# OpenSpindle.net
KiCad netlist of a schematic drawn in EAGLE
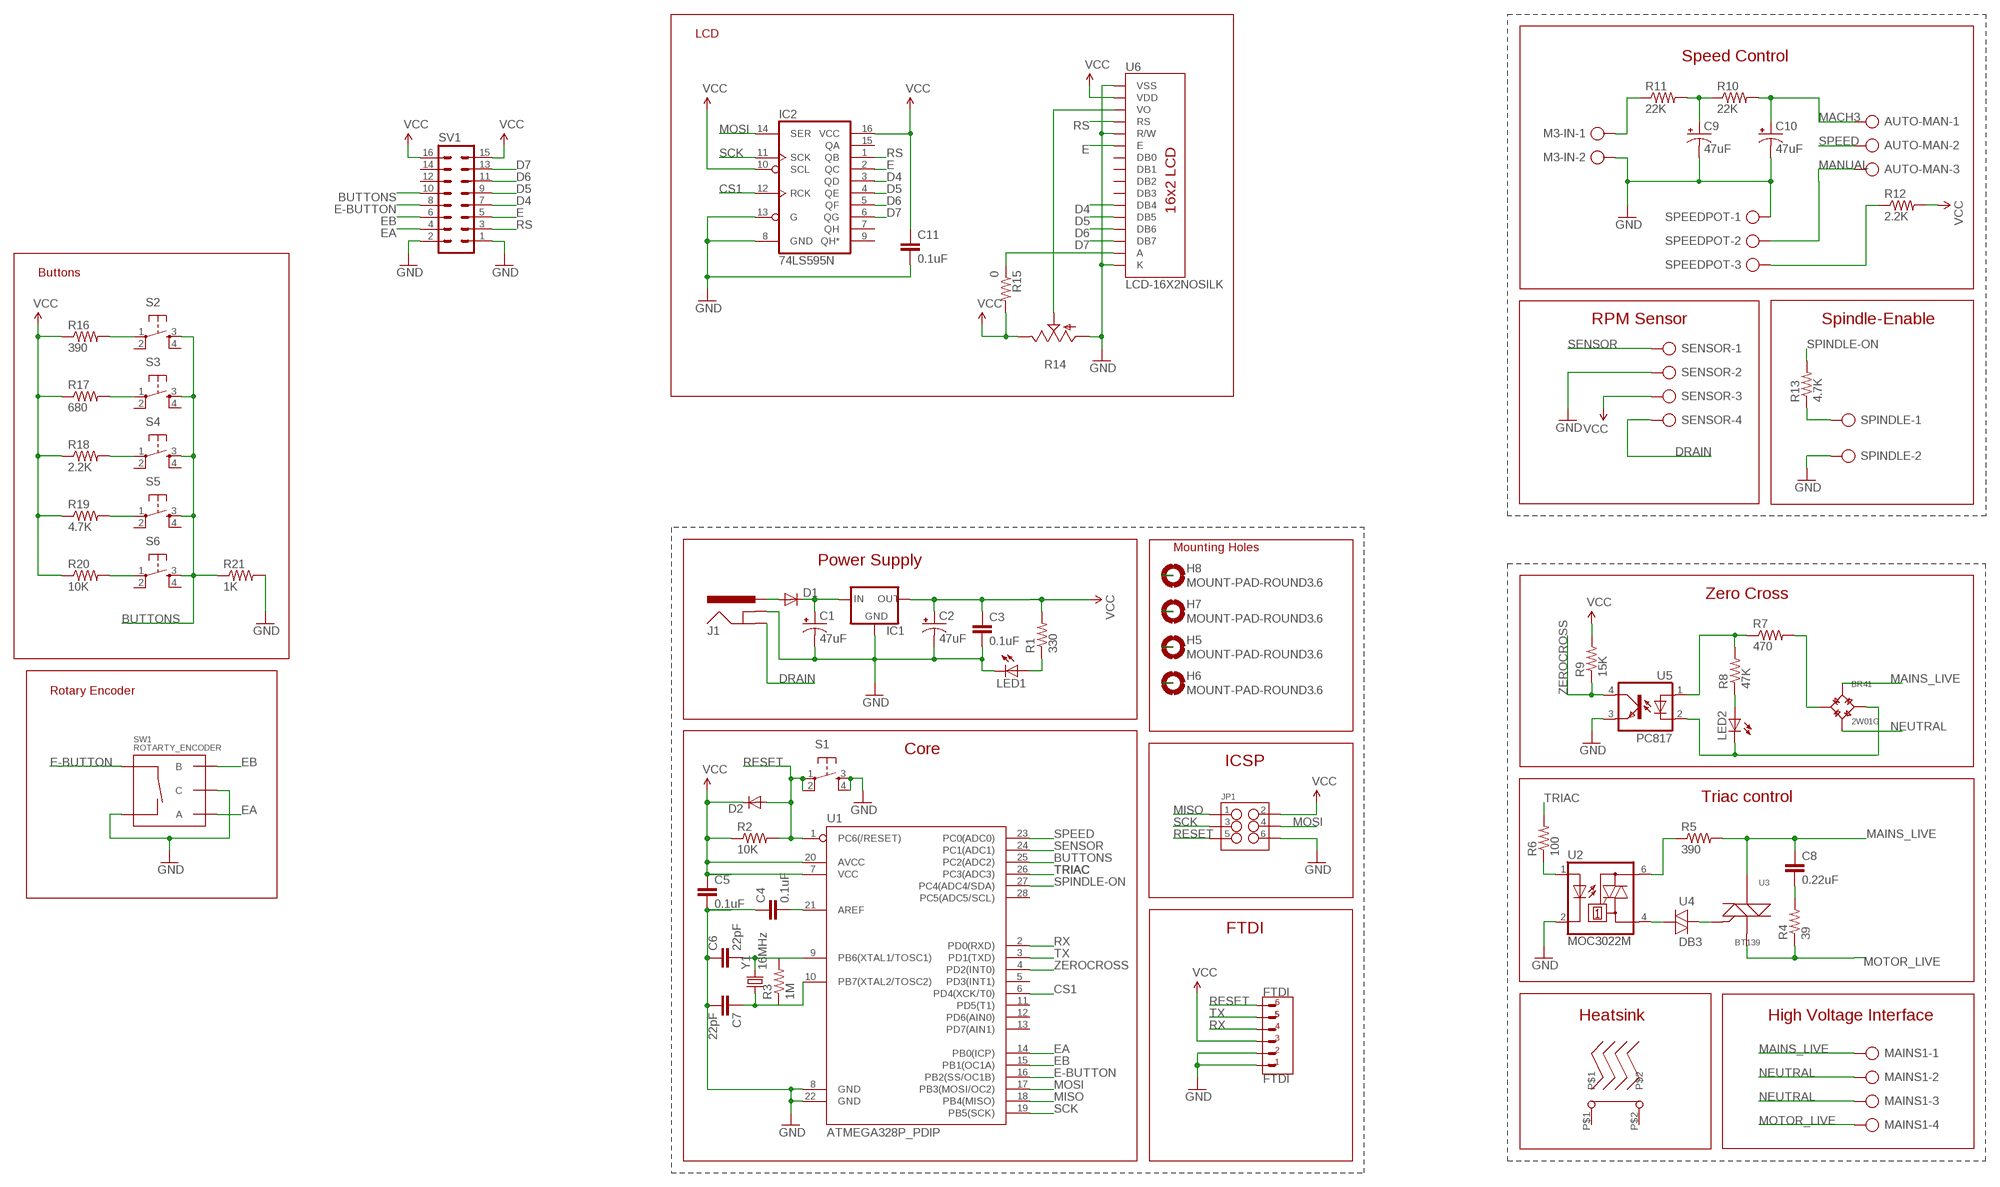
[diagram p0: schematic, sheet 1]

(export (version "E")
  (design (tool "Eeschema 10.0.6"))
  (components
    (comp (ref "AUTO-MAN")
      (value "AK500/3")
      (footprint "eagle-import:AK500_3")
      (libsource (lib "eagle-import") (part "AK500/3"))
    )
    (comp (ref "BR41")
      (value "2W01G")
      (footprint "eagle-import:DIODEBRIDGE")
      (libsource (lib "eagle-import") (part "DIODEBRIDGE"))
    )
    (comp (ref "C1")
      (value "47uF")
      (footprint "eagle-import:CPOL-RADIAL-10UF-25V")
      (libsource (lib "eagle-import") (part "CAP_POLPTH2"))
    )
    (comp (ref "C2")
      (value "47uF")
      (footprint "eagle-import:CPOL-RADIAL-10UF-25V")
      (libsource (lib "eagle-import") (part "CAP_POLPTH2"))
    )
    (comp (ref "C3")
      (value "0.1uF")
      (footprint "eagle-import:CAP-PTH-SMALL")
      (libsource (lib "eagle-import") (part "SparkFun-Capacitors_CAPPTH"))
    )
    (comp (ref "C4")
      (value "0.1uF")
      (footprint "eagle-import:CAP-PTH-SMALL")
      (libsource (lib "eagle-import") (part "SparkFun-Capacitors_CAPPTH"))
    )
    (comp (ref "C5")
      (value "0.1uF")
      (footprint "eagle-import:CAP-PTH-SMALL")
      (libsource (lib "eagle-import") (part "SparkFun-Capacitors_CAPPTH"))
    )
    (comp (ref "C6")
      (value "22pF")
      (footprint "eagle-import:CAP-PTH-SMALL")
      (libsource (lib "eagle-import") (part "SparkFun-Capacitors_CAPPTH"))
    )
    (comp (ref "C7")
      (value "22pF")
      (footprint "eagle-import:CAP-PTH-SMALL")
      (libsource (lib "eagle-import") (part "SparkFun-Capacitors_CAPPTH"))
    )
    (comp (ref "C8")
      (value "0.22uF")
      (footprint "eagle-import:CAP-PTH-SMALL")
      (libsource (lib "eagle-import") (part "CAPPTH"))
    )
    (comp (ref "C9")
      (value "47uF")
      (footprint "eagle-import:CPOL-RADIAL-10UF-25V")
      (libsource (lib "eagle-import") (part "CAP_POLPTH2"))
    )
    (comp (ref "C10")
      (value "47uF")
      (footprint "eagle-import:CPOL-RADIAL-10UF-25V")
      (libsource (lib "eagle-import") (part "CAP_POLPTH2"))
    )
    (comp (ref "C11")
      (value "0.1uF")
      (footprint "eagle-import:CAP-PTH-SMALL")
      (libsource (lib "eagle-import") (part "SparkFun-Capacitors_CAPPTH"))
    )
    (comp (ref "D1")
      (value "DIODEPTH")
      (footprint "eagle-import:DIODE-1N4001")
      (libsource (lib "eagle-import") (part "DIODEPTH"))
    )
    (comp (ref "D2")
      (value "DIODEPTH")
      (footprint "eagle-import:DIODE-1N4001")
      (libsource (lib "eagle-import") (part "DIODEPTH"))
    )
    (comp (ref "FTDI")
      (value "FTDI")
      (footprint "eagle-import:6PINHEADER")
      (libsource (lib "eagle-import") (part "6PINHEADER0.1{dblquote}"))
    )
    (comp (ref "H5")
      (value "MOUNT-PAD-ROUND3.6")
      (footprint "eagle-import:3,6-PAD")
      (libsource (lib "eagle-import") (part "MOUNT-PAD-ROUND3.6"))
    )
    (comp (ref "H6")
      (value "MOUNT-PAD-ROUND3.6")
      (footprint "eagle-import:3,6-PAD")
      (libsource (lib "eagle-import") (part "MOUNT-PAD-ROUND3.6"))
    )
    (comp (ref "H7")
      (value "MOUNT-PAD-ROUND3.6")
      (footprint "eagle-import:3,6-PAD")
      (libsource (lib "eagle-import") (part "MOUNT-PAD-ROUND3.6"))
    )
    (comp (ref "H8")
      (value "MOUNT-PAD-ROUND3.6")
      (footprint "eagle-import:3,6-PAD")
      (libsource (lib "eagle-import") (part "MOUNT-PAD-ROUND3.6"))
    )
    (comp (ref "IC1")
      (value "V_REG_78XX-TO-220")
      (footprint "eagle-import:TO-220-ALT")
      (libsource (lib "eagle-import") (part "V_REG_78XX-TO-220"))
    )
    (comp (ref "IC2")
      (value "74LS595N")
      (footprint "eagle-import:DIL16")
      (libsource (lib "eagle-import") (part "74595NLS"))
    )
    (comp (ref "J1")
      (value "POWER_JACKPTH_LOCK")
      (footprint "eagle-import:POWER_JACK_PTH_LOCK")
      (libsource (lib "eagle-import") (part "POWER_JACKPTH_LOCK"))
    )
    (comp (ref "JP1")
      (value "M03X2POGO_PINS")
      (footprint "eagle-import:2X3_POGO")
      (libsource (lib "eagle-import") (part "M03X2POGO_PINS"))
    )
    (comp (ref "LED1")
      (value "LED5MM")
      (footprint "eagle-import:LED5MM")
      (libsource (lib "eagle-import") (part "adafruit2012_LED5MM"))
    )
    (comp (ref "LED2")
      (value "LED5MM")
      (footprint "eagle-import:LED5MM")
      (libsource (lib "eagle-import") (part "LED5MM"))
    )
    (comp (ref "M3-IN")
      (value "AK500/2")
      (footprint "eagle-import:AK500_2")
      (libsource (lib "eagle-import") (part "AK500/2"))
    )
    (comp (ref "MAINS1")
      (value "AK500/4")
      (footprint "eagle-import:AK500_4")
      (libsource (lib "eagle-import") (part "AK500/4"))
    )
    (comp (ref "R1")
      (value "330")
      (footprint "eagle-import:AXIAL-0.3")
      (libsource (lib "eagle-import") (part "RESISTORAXIAL-0.3"))
    )
    (comp (ref "R2")
      (value "10K")
      (footprint "eagle-import:AXIAL-0.3")
      (libsource (lib "eagle-import") (part "RESISTORAXIAL-0.3"))
    )
    (comp (ref "R3")
      (value "1M")
      (footprint "eagle-import:AXIAL-0.3")
      (libsource (lib "eagle-import") (part "RESISTORAXIAL-0.3"))
    )
    (comp (ref "R4")
      (value "39")
      (footprint "eagle-import:AXIAL-0.3")
      (libsource (lib "eagle-import") (part "RESISTORAXIAL-0.3"))
    )
    (comp (ref "R5")
      (value "390")
      (footprint "eagle-import:AXIAL-0.3")
      (libsource (lib "eagle-import") (part "RESISTORAXIAL-0.3"))
    )
    (comp (ref "R6")
      (value "100")
      (footprint "eagle-import:AXIAL-0.3")
      (libsource (lib "eagle-import") (part "RESISTORAXIAL-0.3"))
    )
    (comp (ref "R7")
      (value "470")
      (footprint "eagle-import:SQM_5-10")
      (libsource (lib "eagle-import") (part "RESISTORM_5-10"))
    )
    (comp (ref "R8")
      (value "47K")
      (footprint "eagle-import:SQM_5-10")
      (libsource (lib "eagle-import") (part "RESISTORM_5-10"))
    )
    (comp (ref "R9")
      (value "15K")
      (footprint "eagle-import:AXIAL-0.3")
      (libsource (lib "eagle-import") (part "RESISTORAXIAL-0.3"))
    )
    (comp (ref "R10")
      (value "22K")
      (footprint "eagle-import:AXIAL-0.3")
      (libsource (lib "eagle-import") (part "RESISTORAXIAL-0.3"))
    )
    (comp (ref "R11")
      (value "22K")
      (footprint "eagle-import:AXIAL-0.3")
      (libsource (lib "eagle-import") (part "RESISTORAXIAL-0.3"))
    )
    (comp (ref "R12")
      (value "2.2K")
      (footprint "eagle-import:AXIAL-0.3")
      (libsource (lib "eagle-import") (part "RESISTORAXIAL-0.3"))
    )
    (comp (ref "R13")
      (value "4.7K")
      (footprint "eagle-import:AXIAL-0.3")
      (libsource (lib "eagle-import") (part "RESISTORAXIAL-0.3"))
    )
    (comp (ref "R14")
      (value "POT_TRIM_US-B25U")
      (footprint "eagle-import:POT_B25U")
      (libsource (lib "eagle-import") (part "POT_TRIM_US-B25U"))
    )
    (comp (ref "R15")
      (value "0")
      (footprint "eagle-import:AXIAL-0.3")
      (libsource (lib "eagle-import") (part "RESISTORAXIAL-0.3"))
    )
    (comp (ref "R16")
      (value "390")
      (footprint "eagle-import:AXIAL-0.3")
      (libsource (lib "eagle-import") (part "RESISTORAXIAL-0.3"))
    )
    (comp (ref "R17")
      (value "680")
      (footprint "eagle-import:AXIAL-0.3")
      (libsource (lib "eagle-import") (part "RESISTORAXIAL-0.3"))
    )
    (comp (ref "R18")
      (value "2.2K")
      (footprint "eagle-import:AXIAL-0.3")
      (libsource (lib "eagle-import") (part "RESISTORAXIAL-0.3"))
    )
    (comp (ref "R19")
      (value "4.7K")
      (footprint "eagle-import:AXIAL-0.3")
      (libsource (lib "eagle-import") (part "RESISTORAXIAL-0.3"))
    )
    (comp (ref "R20")
      (value "10K")
      (footprint "eagle-import:AXIAL-0.3")
      (libsource (lib "eagle-import") (part "RESISTORAXIAL-0.3"))
    )
    (comp (ref "R21")
      (value "1K")
      (footprint "eagle-import:AXIAL-0.3")
      (libsource (lib "eagle-import") (part "RESISTORAXIAL-0.3"))
    )
    (comp (ref "S1")
      (value "TAC_SWITCHPTH")
      (footprint "eagle-import:TACTILE-PTH")
      (libsource (lib "eagle-import") (part "TAC_SWITCHPTH"))
    )
    (comp (ref "S2")
      (value "TAC_SWITCHPTH")
      (footprint "eagle-import:TACTILE-PTH")
      (libsource (lib "eagle-import") (part "TAC_SWITCHPTH"))
    )
    (comp (ref "S3")
      (value "TAC_SWITCHPTH")
      (footprint "eagle-import:TACTILE-PTH")
      (libsource (lib "eagle-import") (part "TAC_SWITCHPTH"))
    )
    (comp (ref "S4")
      (value "TAC_SWITCHPTH")
      (footprint "eagle-import:TACTILE-PTH")
      (libsource (lib "eagle-import") (part "TAC_SWITCHPTH"))
    )
    (comp (ref "S5")
      (value "TAC_SWITCHPTH")
      (footprint "eagle-import:TACTILE-PTH")
      (libsource (lib "eagle-import") (part "TAC_SWITCHPTH"))
    )
    (comp (ref "S6")
      (value "TAC_SWITCHPTH")
      (footprint "eagle-import:TACTILE-PTH")
      (libsource (lib "eagle-import") (part "TAC_SWITCHPTH"))
    )
    (comp (ref "SENSOR")
      (value "AK500/4")
      (footprint "eagle-import:AK500_4")
      (libsource (lib "eagle-import") (part "AK500/4"))
    )
    (comp (ref "SPEEDPOT")
      (value "AK500/3")
      (footprint "eagle-import:AK500_3")
      (libsource (lib "eagle-import") (part "AK500/3"))
    )
    (comp (ref "SPINDLE")
      (value "AK500/2")
      (footprint "eagle-import:AK500_2")
      (libsource (lib "eagle-import") (part "AK500/2"))
    )
    (comp (ref "SV1")
      (value "ML16")
      (footprint "eagle-import:ML16")
      (libsource (lib "eagle-import") (part "ML16"))
    )
    (comp (ref "SW1")
      (value "ROTARTY_ENCODER")
      (footprint "eagle-import:ROTARY_ENC_PLAIN")
      (libsource (lib "eagle-import") (part "ROTARTY_ENCODER"))
    )
    (comp (ref "U$2")
      (value "HEATSINK529802B02500G")
      (footprint "eagle-import:529802B02500G")
      (libsource (lib "eagle-import") (part "HEATSINK529802B02500G"))
    )
    (comp (ref "U1")
      (value "ATMEGA328P_PDIP")
      (footprint "eagle-import:DIL28-3")
      (libsource (lib "eagle-import") (part "ATMEGA328P_PDIP"))
    )
    (comp (ref "U2")
      (value "MOC3022M")
      (footprint "eagle-import:DIL06")
      (fields (field (name "MF") "FAIRCHILD SEMICONDUCTOR") (field (name "MPN") "MOC3022-M"))
      (libsource (lib "eagle-import") (part "MOC30M22"))
    )
    (comp (ref "U3")
      (value "BT139")
      (footprint "eagle-import:TRIAC")
      (libsource (lib "eagle-import") (part "TRIAC"))
    )
    (comp (ref "U4")
      (value "DB3")
      (footprint "eagle-import:DO35-10")
      (libsource (lib "eagle-import") (part "DIAC-DO35-10"))
    )
    (comp (ref "U5")
      (value "PC817")
      (footprint "eagle-import:DIL04")
      (fields (field (name "MPN") "PC817X4J000F"))
      (libsource (lib "eagle-import") (part "PC817"))
    )
    (comp (ref "U6")
      (value "LCD-16X2NOSILK")
      (footprint "eagle-import:LCD-16X2_NOSILK")
      (libsource (lib "eagle-import") (part "LCD-16X2NOSILK"))
    )
    (comp (ref "Y1")
      (value "16MHz")
      (footprint "eagle-import:HC49U-V")
      (libsource (lib "eagle-import") (part "CRYSTALHC49UV"))
    )
  )
  (nets
    (net (code "1") (name "/BUTTONS") (class "Default")
      (node (ref "R21") (pin "P$1") (pinfunction "1_P$1") (pintype "passive"))
      (node (ref "S2") (pin "3") (pinfunction "3_3") (pintype "passive"))
      (node (ref "S3") (pin "3") (pinfunction "3_3") (pintype "passive"))
      (node (ref "S4") (pin "3") (pinfunction "3_3") (pintype "passive"))
      (node (ref "S5") (pin "3") (pinfunction "3_3") (pintype "passive"))
      (node (ref "S6") (pin "3") (pinfunction "3_3") (pintype "passive"))
      (node (ref "SV1") (pin "10") (pinfunction "10_10") (pintype "passive"))
      (node (ref "U1") (pin "25") (pinfunction "PC2(ADC2)_25") (pintype "bidirectional"))
    )
    (net (code "2") (name "/CS1") (class "Default")
      (node (ref "IC2") (pin "12") (pinfunction "RCK_12") (pintype "input"))
      (node (ref "U1") (pin "6") (pinfunction "PD4(XCK/T0)_6") (pintype "bidirectional"))
    )
    (net (code "3") (name "/D4") (class "Default")
      (node (ref "IC2") (pin "3") (pinfunction "QD_3") (pintype "tri_state"))
      (node (ref "SV1") (pin "7") (pinfunction "7_7") (pintype "passive"))
      (node (ref "U6") (pin "11") (pinfunction "DB4_11") (pintype "bidirectional"))
    )
    (net (code "4") (name "/D5") (class "Default")
      (node (ref "IC2") (pin "4") (pinfunction "QE_4") (pintype "tri_state"))
      (node (ref "SV1") (pin "9") (pinfunction "9_9") (pintype "passive"))
      (node (ref "U6") (pin "12") (pinfunction "DB5_12") (pintype "bidirectional"))
    )
    (net (code "5") (name "/D6") (class "Default")
      (node (ref "IC2") (pin "5") (pinfunction "QF_5") (pintype "tri_state"))
      (node (ref "SV1") (pin "11") (pinfunction "11_11") (pintype "passive"))
      (node (ref "U6") (pin "13") (pinfunction "DB6_13") (pintype "bidirectional"))
    )
    (net (code "6") (name "/D7") (class "Default")
      (node (ref "IC2") (pin "6") (pinfunction "QG_6") (pintype "tri_state"))
      (node (ref "SV1") (pin "13") (pinfunction "13_13") (pintype "passive"))
      (node (ref "U6") (pin "14") (pinfunction "DB7_14") (pintype "bidirectional"))
    )
    (net (code "7") (name "/DRAIN") (class "Default")
      (node (ref "J1") (pin "GND") (pinfunction "GND_GND") (pintype "bidirectional"))
      (node (ref "SENSOR") (pin "4") (pinfunction "KL_4") (pintype "passive"))
    )
    (net (code "8") (name "/E") (class "Default")
      (node (ref "IC2") (pin "2") (pinfunction "QC_2") (pintype "tri_state"))
      (node (ref "SV1") (pin "5") (pinfunction "5_5") (pintype "passive"))
      (node (ref "U6") (pin "6") (pinfunction "E_6") (pintype "input"))
    )
    (net (code "9") (name "/E-BUTTON") (class "Default")
      (node (ref "SV1") (pin "8") (pinfunction "8_8") (pintype "passive"))
      (node (ref "SW1") (pin "SW+") (pinfunction "SW+_SW+") (pintype "bidirectional"))
      (node (ref "U1") (pin "16") (pinfunction "PB2(SS/OC1B)_16") (pintype "bidirectional"))
    )
    (net (code "10") (name "/EA") (class "Default")
      (node (ref "SV1") (pin "4") (pinfunction "4_4") (pintype "passive"))
      (node (ref "SW1") (pin "A") (pinfunction "A_A") (pintype "bidirectional"))
      (node (ref "U1") (pin "14") (pinfunction "PB0(ICP)_14") (pintype "bidirectional"))
    )
    (net (code "11") (name "/EB") (class "Default")
      (node (ref "SV1") (pin "6") (pinfunction "6_6") (pintype "passive"))
      (node (ref "SW1") (pin "B") (pinfunction "B_B") (pintype "bidirectional"))
      (node (ref "U1") (pin "15") (pinfunction "PB1(OC1A)_15") (pintype "bidirectional"))
    )
    (net (code "12") (name "/MACH3") (class "Default")
      (node (ref "AUTO-MAN") (pin "1") (pinfunction "KL_1") (pintype "passive"))
      (node (ref "C10") (pin "1") (pinfunction "+_1") (pintype "passive"))
      (node (ref "R10") (pin "P$2") (pinfunction "2_P$2") (pintype "passive"))
    )
    (net (code "13") (name "/MAINS_LIVE") (class "Default")
      (node (ref "BR41") (pin "AC1") (pinfunction "AC1_AC1") (pintype "bidirectional"))
      (node (ref "C8") (pin "1") (pinfunction "1_1") (pintype "passive"))
      (node (ref "MAINS1") (pin "1") (pinfunction "KL_1") (pintype "passive"))
      (node (ref "R5") (pin "P$2") (pinfunction "2_P$2") (pintype "passive"))
      (node (ref "U3") (pin "2") (pinfunction "A_2") (pintype "bidirectional"))
    )
    (net (code "14") (name "/MANUAL") (class "Default")
      (node (ref "AUTO-MAN") (pin "3") (pinfunction "KL_3") (pintype "passive"))
      (node (ref "SPEEDPOT") (pin "2") (pinfunction "KL_2") (pintype "passive"))
    )
    (net (code "15") (name "/MISO") (class "Default")
      (node (ref "JP1") (pin "P$1") (pinfunction "1_P$1") (pintype "bidirectional"))
      (node (ref "U1") (pin "18") (pinfunction "PB4(MISO)_18") (pintype "bidirectional"))
    )
    (net (code "16") (name "/MOSI") (class "Default")
      (node (ref "IC2") (pin "14") (pinfunction "SER_14") (pintype "input"))
      (node (ref "JP1") (pin "P$4") (pinfunction "4_P$4") (pintype "bidirectional"))
      (node (ref "U1") (pin "17") (pinfunction "PB3(MOSI/OC2)_17") (pintype "bidirectional"))
    )
    (net (code "17") (name "/MOTOR_LIVE") (class "Default")
      (node (ref "MAINS1") (pin "4") (pinfunction "KL_4") (pintype "passive"))
      (node (ref "R4") (pin "P$1") (pinfunction "1_P$1") (pintype "passive"))
      (node (ref "U3") (pin "3") (pinfunction "C_3") (pintype "bidirectional"))
    )
    (net (code "18") (name "/NEUTRAL") (class "Default")
      (node (ref "BR41") (pin "AC2") (pinfunction "AC2_AC2") (pintype "bidirectional"))
      (node (ref "MAINS1") (pin "2") (pinfunction "KL_2") (pintype "passive"))
      (node (ref "MAINS1") (pin "3") (pinfunction "KL_3") (pintype "passive"))
    )
    (net (code "19") (name "/P$1") (class "Default")
      (node (ref "U$2") (pin "P$1") (pinfunction "P$1_P$1") (pintype "power_in"))
    )
    (net (code "20") (name "/P$2") (class "Default")
      (node (ref "U$2") (pin "P$2") (pinfunction "P$2_P$2") (pintype "power_in"))
    )
    (net (code "21") (name "/RESET") (class "Default")
      (node (ref "D2") (pin "A") (pinfunction "A_A") (pintype "passive"))
      (node (ref "FTDI") (pin "P$6") (pinfunction "P$6_P$6") (pintype "bidirectional"))
      (node (ref "JP1") (pin "P$5") (pinfunction "5_P$5") (pintype "bidirectional"))
      (node (ref "R2") (pin "P$2") (pinfunction "2_P$2") (pintype "passive"))
      (node (ref "S1") (pin "1") (pinfunction "1_1") (pintype "passive"))
      (node (ref "S1") (pin "2") (pinfunction "2_2") (pintype "passive"))
      (node (ref "U1") (pin "1") (pinfunction "PC6(/RESET)_1") (pintype "bidirectional"))
    )
    (net (code "22") (name "/RS") (class "Default")
      (node (ref "IC2") (pin "1") (pinfunction "QB_1") (pintype "tri_state"))
      (node (ref "SV1") (pin "3") (pinfunction "3_3") (pintype "passive"))
      (node (ref "U6") (pin "4") (pinfunction "RS_4") (pintype "input"))
    )
    (net (code "23") (name "/RX") (class "Default")
      (node (ref "FTDI") (pin "P$4") (pinfunction "P$4_P$4") (pintype "bidirectional"))
      (node (ref "U1") (pin "2") (pinfunction "PD0(RXD)_2") (pintype "bidirectional"))
    )
    (net (code "24") (name "/SCK") (class "Default")
      (node (ref "IC2") (pin "11") (pinfunction "SCK_11") (pintype "input"))
      (node (ref "JP1") (pin "P$3") (pinfunction "3_P$3") (pintype "bidirectional"))
      (node (ref "U1") (pin "19") (pinfunction "PB5(SCK)_19") (pintype "bidirectional"))
    )
    (net (code "25") (name "/SENSOR") (class "Default")
      (node (ref "SENSOR") (pin "1") (pinfunction "KL_1") (pintype "passive"))
      (node (ref "U1") (pin "24") (pinfunction "PC1(ADC1)_24") (pintype "bidirectional"))
    )
    (net (code "26") (name "/SPEED") (class "Default")
      (node (ref "AUTO-MAN") (pin "2") (pinfunction "KL_2") (pintype "passive"))
      (node (ref "U1") (pin "23") (pinfunction "PC0(ADC0)_23") (pintype "bidirectional"))
    )
    (net (code "27") (name "/SPINDLE-ON") (class "Default")
      (node (ref "R13") (pin "P$2") (pinfunction "2_P$2") (pintype "passive"))
      (node (ref "U1") (pin "27") (pinfunction "PC4(ADC4/SDA)_27") (pintype "bidirectional"))
    )
    (net (code "28") (name "/TRIAC") (class "Default")
      (node (ref "R6") (pin "P$2") (pinfunction "2_P$2") (pintype "passive"))
      (node (ref "U1") (pin "26") (pinfunction "PC3(ADC3)_26") (pintype "bidirectional"))
    )
    (net (code "29") (name "/TX") (class "Default")
      (node (ref "FTDI") (pin "P$5") (pinfunction "P$5_P$5") (pintype "bidirectional"))
      (node (ref "U1") (pin "3") (pinfunction "PD1(TXD)_3") (pintype "bidirectional"))
    )
    (net (code "30") (name "/ZEROCROSS") (class "Default")
      (node (ref "R9") (pin "P$1") (pinfunction "1_P$1") (pintype "passive"))
      (node (ref "U1") (pin "4") (pinfunction "PD2(INT0)_4") (pintype "bidirectional"))
      (node (ref "U5") (pin "4") (pinfunction "COL_4") (pintype "passive"))
    )
    (net (code "31") (name "GND") (class "Default")
      (node (ref "C1") (pin "2") (pinfunction "-_2") (pintype "passive"))
      (node (ref "C10") (pin "2") (pinfunction "-_2") (pintype "passive"))
      (node (ref "C11") (pin "2") (pinfunction "2_2") (pintype "passive"))
      (node (ref "C2") (pin "2") (pinfunction "-_2") (pintype "passive"))
      (node (ref "C3") (pin "2") (pinfunction "2_2") (pintype "passive"))
      (node (ref "C4") (pin "1") (pinfunction "1_1") (pintype "passive"))
      (node (ref "C5") (pin "2") (pinfunction "2_2") (pintype "passive"))
      (node (ref "C6") (pin "1") (pinfunction "1_1") (pintype "passive"))
      (node (ref "C7") (pin "2") (pinfunction "2_2") (pintype "passive"))
      (node (ref "C9") (pin "2") (pinfunction "-_2") (pintype "passive"))
      (node (ref "FTDI") (pin "P$1") (pinfunction "P$1_P$1") (pintype "bidirectional"))
      (node (ref "FTDI") (pin "P$2") (pinfunction "P$2_P$2") (pintype "bidirectional"))
      (node (ref "IC1") (pin "GND") (pinfunction "GND_GND") (pintype "input"))
      (node (ref "IC2") (pin "13") (pinfunction "G_13") (pintype "input"))
      (node (ref "IC2") (pin "8") (pinfunction "GND_8") (pintype "power_in"))
      (node (ref "J1") (pin "GNDBREAK") (pinfunction "GNDBREAK_GNDBREAK") (pintype "bidirectional"))
      (node (ref "JP1") (pin "P$6") (pinfunction "6_P$6") (pintype "bidirectional"))
      (node (ref "LED1") (pin "K") (pinfunction "C_K") (pintype "passive"))
      (node (ref "M3-IN") (pin "2") (pinfunction "KL_2") (pintype "passive"))
      (node (ref "R14") (pin "A") (pinfunction "A_A") (pintype "passive"))
      (node (ref "R21") (pin "P$2") (pinfunction "2_P$2") (pintype "passive"))
      (node (ref "S1") (pin "3") (pinfunction "3_3") (pintype "passive"))
      (node (ref "S1") (pin "4") (pinfunction "4_4") (pintype "passive"))
      (node (ref "SENSOR") (pin "2") (pinfunction "KL_2") (pintype "passive"))
      (node (ref "SPEEDPOT") (pin "1") (pinfunction "KL_1") (pintype "passive"))
      (node (ref "SPINDLE") (pin "2") (pinfunction "KL_2") (pintype "passive"))
      (node (ref "SV1") (pin "1") (pinfunction "1_1") (pintype "passive"))
      (node (ref "SV1") (pin "2") (pinfunction "2_2") (pintype "passive"))
      (node (ref "SW1") (pin "C") (pinfunction "C_C") (pintype "bidirectional"))
      (node (ref "SW1") (pin "SW-") (pinfunction "SW-_SW-") (pintype "bidirectional"))
      (node (ref "U1") (pin "22") (pinfunction "GND_22") (pintype "bidirectional"))
      (node (ref "U1") (pin "8") (pinfunction "GND_8") (pintype "bidirectional"))
      (node (ref "U2") (pin "2") (pinfunction "C_2") (pintype "passive"))
      (node (ref "U5") (pin "3") (pinfunction "EMIT_3") (pintype "passive"))
      (node (ref "U6") (pin "1") (pinfunction "VSS_1") (pintype "power_in"))
      (node (ref "U6") (pin "16") (pinfunction "K_16") (pintype "power_in"))
      (node (ref "U6") (pin "5") (pinfunction "R/W_5") (pintype "input"))
    )
    (net (code "32") (name "Net-(C1-+)") (class "Default")
      (node (ref "C1") (pin "1") (pinfunction "+_1") (pintype "passive"))
      (node (ref "D1") (pin "C") (pinfunction "C_C") (pintype "passive"))
      (node (ref "IC1") (pin "IN") (pinfunction "IN_IN") (pintype "input"))
    )
    (net (code "33") (name "Net-(C9-+)") (class "Default")
      (node (ref "C9") (pin "1") (pinfunction "+_1") (pintype "passive"))
      (node (ref "R10") (pin "P$1") (pinfunction "1_P$1") (pintype "passive"))
      (node (ref "R11") (pin "P$2") (pinfunction "2_P$2") (pintype "passive"))
    )
    (net (code "34") (name "Net-(D1-PadA)") (class "Default")
      (node (ref "D1") (pin "A") (pinfunction "A_A") (pintype "passive"))
      (node (ref "J1") (pin "PWR") (pinfunction "PWR_PWR") (pintype "bidirectional"))
    )
    (net (code "35") (name "Net-(LED2-C)") (class "Default")
      (node (ref "BR41") (pin "-") (pinfunction "-_-") (pintype "bidirectional"))
      (node (ref "LED2") (pin "K") (pinfunction "C_K") (pintype "passive"))
      (node (ref "U5") (pin "2") (pinfunction "C_2") (pintype "passive"))
    )
    (net (code "36") (name "Net-(M3-INA-KL)") (class "Default")
      (node (ref "M3-IN") (pin "1") (pinfunction "KL_1") (pintype "passive"))
      (node (ref "R11") (pin "P$1") (pinfunction "1_P$1") (pintype "passive"))
    )
    (net (code "37") (name "Net-(R1-1)") (class "Default")
      (node (ref "LED1") (pin "A") (pinfunction "A_A") (pintype "passive"))
      (node (ref "R1") (pin "P$1") (pinfunction "1_P$1") (pintype "passive"))
    )
    (net (code "38") (name "Net-(R3-1)") (class "Default")
      (node (ref "C7") (pin "1") (pinfunction "1_1") (pintype "passive"))
      (node (ref "R3") (pin "P$1") (pinfunction "1_P$1") (pintype "passive"))
      (node (ref "U1") (pin "10") (pinfunction "PB7(XTAL2/TOSC2)_10") (pintype "bidirectional"))
      (node (ref "Y1") (pin "1") (pinfunction "1_1") (pintype "passive"))
    )
    (net (code "39") (name "Net-(R3-2)") (class "Default")
      (node (ref "C6") (pin "2") (pinfunction "2_2") (pintype "passive"))
      (node (ref "R3") (pin "P$2") (pinfunction "2_P$2") (pintype "passive"))
      (node (ref "U1") (pin "9") (pinfunction "PB6(XTAL1/TOSC1)_9") (pintype "bidirectional"))
      (node (ref "Y1") (pin "2") (pinfunction "2_2") (pintype "passive"))
    )
    (net (code "40") (name "Net-(R4-2)") (class "Default")
      (node (ref "C8") (pin "2") (pinfunction "2_2") (pintype "passive"))
      (node (ref "R4") (pin "P$2") (pinfunction "2_P$2") (pintype "passive"))
    )
    (net (code "41") (name "Net-(R5-1)") (class "Default")
      (node (ref "R5") (pin "P$1") (pinfunction "1_P$1") (pintype "passive"))
      (node (ref "U2") (pin "6") (pinfunction "A2_6") (pintype "passive"))
    )
    (net (code "42") (name "Net-(R6-1)") (class "Default")
      (node (ref "R6") (pin "P$1") (pinfunction "1_P$1") (pintype "passive"))
      (node (ref "U2") (pin "1") (pinfunction "A_1") (pintype "passive"))
    )
    (net (code "43") (name "Net-(R7-1)") (class "Default")
      (node (ref "R7") (pin "P1") (pinfunction "1_P1") (pintype "passive"))
      (node (ref "R8") (pin "P2") (pinfunction "2_P2") (pintype "passive"))
      (node (ref "U5") (pin "1") (pinfunction "A_1") (pintype "passive"))
    )
    (net (code "44") (name "Net-(R7-2)") (class "Default")
      (node (ref "BR41") (pin "+") (pinfunction "+_+") (pintype "bidirectional"))
      (node (ref "R7") (pin "P2") (pinfunction "2_P2") (pintype "passive"))
    )
    (net (code "45") (name "Net-(R8-1)") (class "Default")
      (node (ref "LED2") (pin "A") (pinfunction "A_A") (pintype "passive"))
      (node (ref "R8") (pin "P1") (pinfunction "1_P1") (pintype "passive"))
    )
    (net (code "46") (name "Net-(R12-1)") (class "Default")
      (node (ref "R12") (pin "P$1") (pinfunction "1_P$1") (pintype "passive"))
      (node (ref "SPEEDPOT") (pin "3") (pinfunction "KL_3") (pintype "passive"))
    )
    (net (code "47") (name "Net-(R13-1)") (class "Default")
      (node (ref "R13") (pin "P$1") (pinfunction "1_P$1") (pintype "passive"))
      (node (ref "SPINDLE") (pin "1") (pinfunction "KL_1") (pintype "passive"))
    )
    (net (code "48") (name "Net-(R15-1)") (class "Default")
      (node (ref "R15") (pin "P$1") (pinfunction "1_P$1") (pintype "passive"))
      (node (ref "U6") (pin "15") (pinfunction "A_15") (pintype "power_in"))
    )
    (net (code "49") (name "Net-(R16-2)") (class "Default")
      (node (ref "R16") (pin "P$2") (pinfunction "2_P$2") (pintype "passive"))
      (node (ref "S2") (pin "1") (pinfunction "1_1") (pintype "passive"))
    )
    (net (code "50") (name "Net-(R17-2)") (class "Default")
      (node (ref "R17") (pin "P$2") (pinfunction "2_P$2") (pintype "passive"))
      (node (ref "S3") (pin "1") (pinfunction "1_1") (pintype "passive"))
    )
    (net (code "51") (name "Net-(R18-2)") (class "Default")
      (node (ref "R18") (pin "P$2") (pinfunction "2_P$2") (pintype "passive"))
      (node (ref "S4") (pin "1") (pinfunction "1_1") (pintype "passive"))
    )
    (net (code "52") (name "Net-(R19-2)") (class "Default")
      (node (ref "R19") (pin "P$2") (pinfunction "2_P$2") (pintype "passive"))
      (node (ref "S5") (pin "1") (pinfunction "1_1") (pintype "passive"))
    )
    (net (code "53") (name "Net-(R20-2)") (class "Default")
      (node (ref "R20") (pin "P$2") (pinfunction "2_P$2") (pintype "passive"))
      (node (ref "S6") (pin "1") (pinfunction "1_1") (pintype "passive"))
    )
    (net (code "54") (name "Net-(U1-AREF)") (class "Default")
      (node (ref "C4") (pin "2") (pinfunction "2_2") (pintype "passive"))
      (node (ref "U1") (pin "21") (pinfunction "AREF_21") (pintype "bidirectional"))
    )
    (net (code "55") (name "Net-(U2-A1)") (class "Default")
      (node (ref "U2") (pin "4") (pinfunction "A1_4") (pintype "passive"))
      (node (ref "U4") (pin "A") (pinfunction "1_A") (pintype "passive"))
    )
    (net (code "56") (name "Net-(U3-B)") (class "Default")
      (node (ref "U3") (pin "1") (pinfunction "B_1") (pintype "bidirectional"))
      (node (ref "U4") (pin "C") (pinfunction "2_C") (pintype "passive"))
    )
    (net (code "57") (name "Net-(U6-VO)") (class "Default")
      (node (ref "R14") (pin "S") (pinfunction "S_S") (pintype "passive"))
      (node (ref "U6") (pin "3") (pinfunction "VO_3") (pintype "bidirectional"))
    )
    (net (code "58") (name "VCC") (class "Default")
      (node (ref "C11") (pin "1") (pinfunction "1_1") (pintype "passive"))
      (node (ref "C2") (pin "1") (pinfunction "+_1") (pintype "passive"))
      (node (ref "C3") (pin "1") (pinfunction "1_1") (pintype "passive"))
      (node (ref "C5") (pin "1") (pinfunction "1_1") (pintype "passive"))
      (node (ref "D2") (pin "C") (pinfunction "C_C") (pintype "passive"))
      (node (ref "FTDI") (pin "P$3") (pinfunction "P$3_P$3") (pintype "bidirectional"))
      (node (ref "IC1") (pin "OUT") (pinfunction "OUT_OUT") (pintype "output"))
      (node (ref "IC2") (pin "10") (pinfunction "SCL_10") (pintype "input"))
      (node (ref "IC2") (pin "16") (pinfunction "VCC_16") (pintype "power_in"))
      (node (ref "JP1") (pin "P$2") (pinfunction "2_P$2") (pintype "bidirectional"))
      (node (ref "R1") (pin "P$2") (pinfunction "2_P$2") (pintype "passive"))
      (node (ref "R12") (pin "P$2") (pinfunction "2_P$2") (pintype "passive"))
      (node (ref "R14") (pin "E") (pinfunction "E_E") (pintype "passive"))
      (node (ref "R15") (pin "P$2") (pinfunction "2_P$2") (pintype "passive"))
      (node (ref "R16") (pin "P$1") (pinfunction "1_P$1") (pintype "passive"))
      (node (ref "R17") (pin "P$1") (pinfunction "1_P$1") (pintype "passive"))
      (node (ref "R18") (pin "P$1") (pinfunction "1_P$1") (pintype "passive"))
      (node (ref "R19") (pin "P$1") (pinfunction "1_P$1") (pintype "passive"))
      (node (ref "R2") (pin "P$1") (pinfunction "1_P$1") (pintype "passive"))
      (node (ref "R20") (pin "P$1") (pinfunction "1_P$1") (pintype "passive"))
      (node (ref "R9") (pin "P$2") (pinfunction "2_P$2") (pintype "passive"))
      (node (ref "SENSOR") (pin "3") (pinfunction "KL_3") (pintype "passive"))
      (node (ref "SV1") (pin "15") (pinfunction "15_15") (pintype "passive"))
      (node (ref "SV1") (pin "16") (pinfunction "16_16") (pintype "passive"))
      (node (ref "U1") (pin "20") (pinfunction "AVCC_20") (pintype "bidirectional"))
      (node (ref "U1") (pin "7") (pinfunction "VCC_7") (pintype "bidirectional"))
      (node (ref "U6") (pin "2") (pinfunction "VDD_2") (pintype "power_in"))
    )
    (net (code "59") (name "unconnected-(H5-MOUNT-PadB3,6)") (class "Default")
      (node (ref "H5") (pin "B3,6") (pinfunction "MOUNT_B3,6") (pintype "passive"))
    )
    (net (code "60") (name "unconnected-(H6-MOUNT-PadB3,6)") (class "Default")
      (node (ref "H6") (pin "B3,6") (pinfunction "MOUNT_B3,6") (pintype "passive"))
    )
    (net (code "61") (name "unconnected-(H7-MOUNT-PadB3,6)") (class "Default")
      (node (ref "H7") (pin "B3,6") (pinfunction "MOUNT_B3,6") (pintype "passive"))
    )
    (net (code "62") (name "unconnected-(H8-MOUNT-PadB3,6)") (class "Default")
      (node (ref "H8") (pin "B3,6") (pinfunction "MOUNT_B3,6") (pintype "passive"))
    )
    (net (code "63") (name "unconnected-(IC2-QA-Pad15)") (class "Default")
      (node (ref "IC2") (pin "15") (pinfunction "QA_15") (pintype "tri_state"))
    )
    (net (code "64") (name "unconnected-(IC2-QH*-Pad9)") (class "Default")
      (node (ref "IC2") (pin "9") (pinfunction "QH*_9") (pintype "tri_state"))
    )
    (net (code "65") (name "unconnected-(IC2-QH-Pad7)") (class "Default")
      (node (ref "IC2") (pin "7") (pinfunction "QH_7") (pintype "tri_state"))
    )
    (net (code "66") (name "unconnected-(S2-Pad2)") (class "Default")
      (node (ref "S2") (pin "2") (pinfunction "2_2") (pintype "passive"))
    )
    (net (code "67") (name "unconnected-(S2-Pad4)") (class "Default")
      (node (ref "S2") (pin "4") (pinfunction "4_4") (pintype "passive"))
    )
    (net (code "68") (name "unconnected-(S3-Pad2)") (class "Default")
      (node (ref "S3") (pin "2") (pinfunction "2_2") (pintype "passive"))
    )
    (net (code "69") (name "unconnected-(S3-Pad4)") (class "Default")
      (node (ref "S3") (pin "4") (pinfunction "4_4") (pintype "passive"))
    )
    (net (code "70") (name "unconnected-(S4-Pad2)") (class "Default")
      (node (ref "S4") (pin "2") (pinfunction "2_2") (pintype "passive"))
    )
    (net (code "71") (name "unconnected-(S4-Pad4)") (class "Default")
      (node (ref "S4") (pin "4") (pinfunction "4_4") (pintype "passive"))
    )
    (net (code "72") (name "unconnected-(S5-Pad2)") (class "Default")
      (node (ref "S5") (pin "2") (pinfunction "2_2") (pintype "passive"))
    )
    (net (code "73") (name "unconnected-(S5-Pad4)") (class "Default")
      (node (ref "S5") (pin "4") (pinfunction "4_4") (pintype "passive"))
    )
    (net (code "74") (name "unconnected-(S6-Pad2)") (class "Default")
      (node (ref "S6") (pin "2") (pinfunction "2_2") (pintype "passive"))
    )
    (net (code "75") (name "unconnected-(S6-Pad4)") (class "Default")
      (node (ref "S6") (pin "4") (pinfunction "4_4") (pintype "passive"))
    )
    (net (code "76") (name "unconnected-(SV1-Pad12)") (class "Default")
      (node (ref "SV1") (pin "12") (pinfunction "12_12") (pintype "passive"))
    )
    (net (code "77") (name "unconnected-(SV1-Pad14)") (class "Default")
      (node (ref "SV1") (pin "14") (pinfunction "14_14") (pintype "passive"))
    )
    (net (code "78") (name "unconnected-(U1-PC5(ADC5{slash}SCL)-Pad28)") (class "Default")
      (node (ref "U1") (pin "28") (pinfunction "PC5(ADC5/SCL)_28") (pintype "bidirectional"))
    )
    (net (code "79") (name "unconnected-(U1-PD3(INT1)-Pad5)") (class "Default")
      (node (ref "U1") (pin "5") (pinfunction "PD3(INT1)_5") (pintype "bidirectional"))
    )
    (net (code "80") (name "unconnected-(U1-PD5(T1)-Pad11)") (class "Default")
      (node (ref "U1") (pin "11") (pinfunction "PD5(T1)_11") (pintype "bidirectional"))
    )
    (net (code "81") (name "unconnected-(U1-PD6(AIN0)-Pad12)") (class "Default")
      (node (ref "U1") (pin "12") (pinfunction "PD6(AIN0)_12") (pintype "bidirectional"))
    )
    (net (code "82") (name "unconnected-(U1-PD7(AIN1)-Pad13)") (class "Default")
      (node (ref "U1") (pin "13") (pinfunction "PD7(AIN1)_13") (pintype "bidirectional"))
    )
    (net (code "83") (name "unconnected-(U6-DB0-Pad7)") (class "Default")
      (node (ref "U6") (pin "7") (pinfunction "DB0_7") (pintype "bidirectional"))
    )
    (net (code "84") (name "unconnected-(U6-DB1-Pad8)") (class "Default")
      (node (ref "U6") (pin "8") (pinfunction "DB1_8") (pintype "bidirectional"))
    )
    (net (code "85") (name "unconnected-(U6-DB2-Pad9)") (class "Default")
      (node (ref "U6") (pin "9") (pinfunction "DB2_9") (pintype "bidirectional"))
    )
    (net (code "86") (name "unconnected-(U6-DB3-Pad10)") (class "Default")
      (node (ref "U6") (pin "10") (pinfunction "DB3_10") (pintype "bidirectional"))
    )
  )
)
